# queso_dip_v4.net
KiCad netlist of a schematic drawn in EAGLE
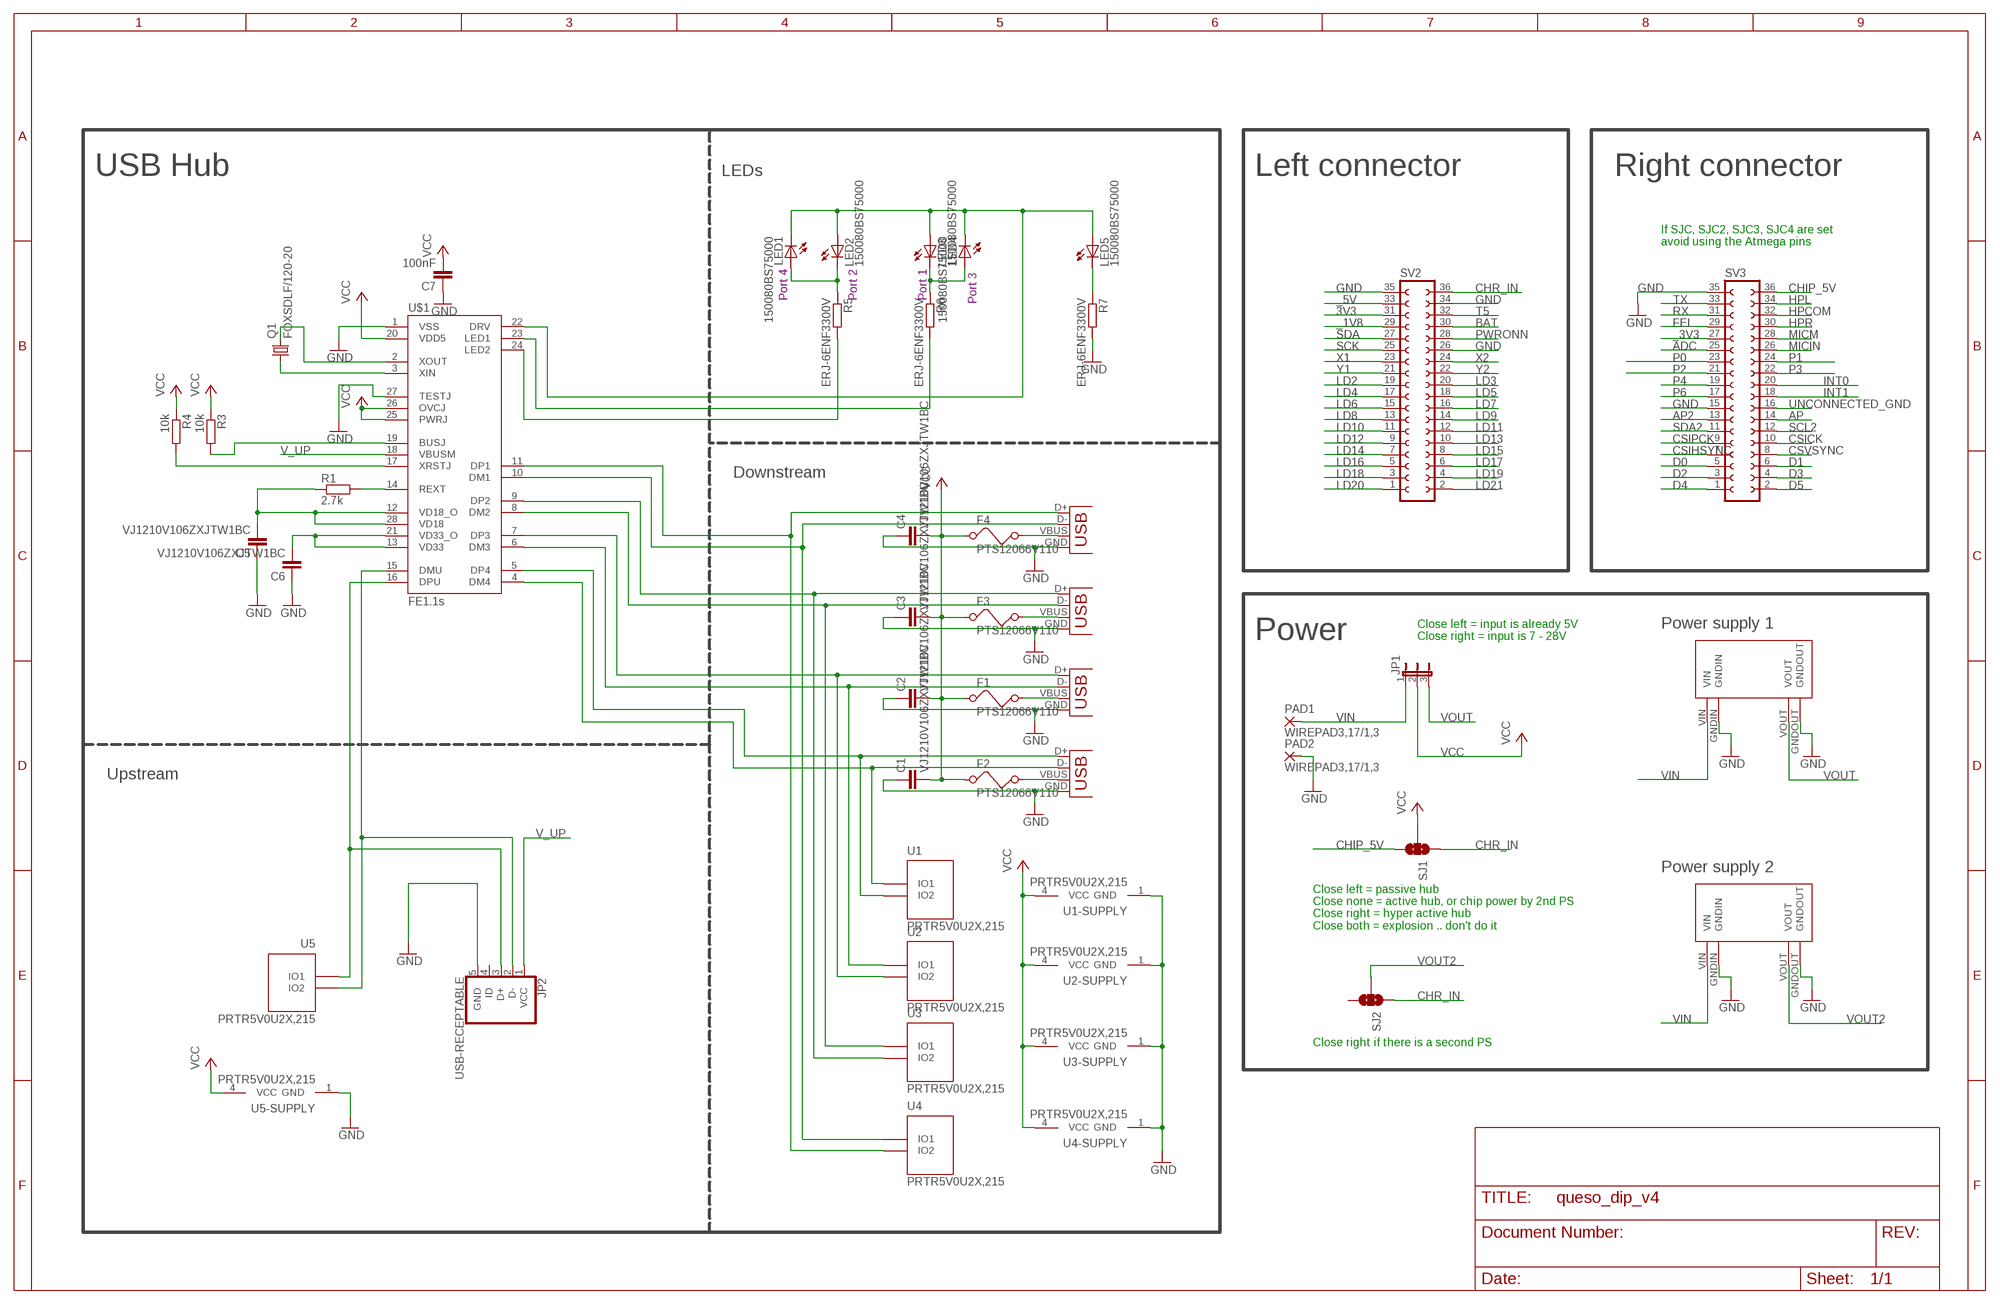
[diagram p0: schematic, sheet 1]

(export (version "E")
  (design (tool "Eeschema 10.0.6"))
  (components
    (comp (ref "C1")
      (value "VJ1210V106ZXJTW1BC")
      (footprint "eagle-import:C1210")
      (libsource (lib "eagle-import") (part "C-EUC1210"))
    )
    (comp (ref "C2")
      (value "VJ1210V106ZXJTW1BC")
      (footprint "eagle-import:C1210")
      (libsource (lib "eagle-import") (part "C-EUC1210"))
    )
    (comp (ref "C3")
      (value "VJ1210V106ZXJTW1BC")
      (footprint "eagle-import:C1210")
      (libsource (lib "eagle-import") (part "C-EUC1210"))
    )
    (comp (ref "C4")
      (value "VJ1210V106ZXJTW1BC")
      (footprint "eagle-import:C1210")
      (libsource (lib "eagle-import") (part "C-EUC1210"))
    )
    (comp (ref "C5")
      (value "VJ1210V106ZXJTW1BC")
      (footprint "eagle-import:C1210")
      (libsource (lib "eagle-import") (part "C-EUC1210"))
    )
    (comp (ref "C6")
      (value "VJ1210V106ZXJTW1BC")
      (footprint "eagle-import:C1210")
      (libsource (lib "eagle-import") (part "C-EUC1210"))
    )
    (comp (ref "C7")
      (value "100nF")
      (footprint "eagle-import:C0805")
      (libsource (lib "eagle-import") (part "C-EUC0805"))
    )
    (comp (ref "F1")
      (value "PTS12066V110")
      (footprint "eagle-import:1210")
      (libsource (lib "eagle-import") (part "FUSED"))
    )
    (comp (ref "F2")
      (value "PTS12066V110")
      (footprint "eagle-import:1210")
      (libsource (lib "eagle-import") (part "FUSED"))
    )
    (comp (ref "F3")
      (value "PTS12066V110")
      (footprint "eagle-import:1210")
      (libsource (lib "eagle-import") (part "FUSED"))
    )
    (comp (ref "F4")
      (value "PTS12066V110")
      (footprint "eagle-import:1210")
      (libsource (lib "eagle-import") (part "FUSED"))
    )
    (comp (ref "JP1")
      (value "JP2E")
      (footprint "eagle-import:JP2")
      (libsource (lib "eagle-import") (part "JP2E"))
    )
    (comp (ref "JP2")
      (value "USB-RECEPTABLE")
      (footprint "eagle-import:FCI-10103594-0001LF")
      (libsource (lib "eagle-import") (part "USB-RECEPTABLE"))
    )
    (comp (ref "LED1")
      (value "150080BS75000")
      (footprint "eagle-import:CHIP-LED0805")
      (libsource (lib "eagle-import") (part "LEDCHIP-LED0805"))
    )
    (comp (ref "LED2")
      (value "150080BS75000")
      (footprint "eagle-import:CHIP-LED0805")
      (libsource (lib "eagle-import") (part "LEDCHIP-LED0805"))
    )
    (comp (ref "LED3")
      (value "150080BS75000")
      (footprint "eagle-import:CHIP-LED0805")
      (libsource (lib "eagle-import") (part "LEDCHIP-LED0805"))
    )
    (comp (ref "LED4")
      (value "150080BS75000")
      (footprint "eagle-import:CHIP-LED0805")
      (libsource (lib "eagle-import") (part "LEDCHIP-LED0805"))
    )
    (comp (ref "LED5")
      (value "150080BS75000")
      (footprint "eagle-import:CHIP-LED0805")
      (libsource (lib "eagle-import") (part "LEDCHIP-LED0805"))
    )
    (comp (ref "PAD1")
      (value "WIREPAD3,17/1,3")
      (footprint "eagle-import:3,17_1,3")
      (libsource (lib "eagle-import") (part "WIREPAD3,17/1,3"))
    )
    (comp (ref "PAD2")
      (value "WIREPAD3,17/1,3")
      (footprint "eagle-import:3,17_1,3")
      (libsource (lib "eagle-import") (part "WIREPAD3,17/1,3"))
    )
    (comp (ref "Q1")
      (value "FOXSDLF/120-20")
      (footprint "eagle-import:SM49")
      (libsource (lib "eagle-import") (part "CRYSTALSM49"))
    )
    (comp (ref "R1")
      (value "2.7k")
      (footprint "eagle-import:R0805")
      (libsource (lib "eagle-import") (part "R-EU_R0805"))
    )
    (comp (ref "R3")
      (value "10k")
      (footprint "eagle-import:R0805")
      (libsource (lib "eagle-import") (part "R-EU_R0805"))
    )
    (comp (ref "R4")
      (value "10k")
      (footprint "eagle-import:R0805")
      (libsource (lib "eagle-import") (part "R-EU_R0805"))
    )
    (comp (ref "R5")
      (value "ERJ-6ENF3300V")
      (footprint "eagle-import:R0805")
      (libsource (lib "eagle-import") (part "R-EU_R0805"))
    )
    (comp (ref "R6")
      (value "ERJ-6ENF3300V")
      (footprint "eagle-import:R0805")
      (libsource (lib "eagle-import") (part "R-EU_R0805"))
    )
    (comp (ref "R7")
      (value "ERJ-6ENF3300V")
      (footprint "eagle-import:R0805")
      (libsource (lib "eagle-import") (part "R-EU_R0805"))
    )
    (comp (ref "SJ1")
      (value "SOLDERJUMPER_2WAYT")
      (footprint "eagle-import:SJ_2")
      (libsource (lib "eagle-import") (part "SOLDERJUMPER_2WAYT"))
    )
    (comp (ref "SJ2")
      (value "SOLDERJUMPER_2WAYT")
      (footprint "eagle-import:SJ_2")
      (libsource (lib "eagle-import") (part "SOLDERJUMPER_2WAYT"))
    )
    (comp (ref "SV2")
      (value "FE18-2")
      (footprint "eagle-import:FE18-2")
      (libsource (lib "eagle-import") (part "FE18-2"))
    )
    (comp (ref "SV3")
      (value "FE18-2")
      (footprint "eagle-import:FE18-2")
      (libsource (lib "eagle-import") (part "FE18-2"))
    )
    (comp (ref "U$1")
      (value "FE1.1S")
      (footprint "eagle-import:FE1.1S_SSOP-28")
      (libsource (lib "eagle-import") (part "FE1.1S"))
    )
    (comp (ref "U$3")
      (value "MP1584EN")
      (footprint "eagle-import:MP1584EN")
      (libsource (lib "eagle-import") (part "MP1584EN"))
    )
    (comp (ref "U$9")
      (value "MP1584EN")
      (footprint "eagle-import:MP1584EN")
      (libsource (lib "eagle-import") (part "MP1584EN"))
    )
    (comp (ref "U1")
      (value "PRTR5V0U2X,215")
      (footprint "eagle-import:SOT-143B")
      (fields (field (name "MANUFACTURER") "NXP Semiconductors"))
      (libsource (lib "eagle-import") (part "PRTR5V0U2X?"))
    )
    (comp (ref "U2")
      (value "PRTR5V0U2X,215")
      (footprint "eagle-import:SOT-143B")
      (fields (field (name "MANUFACTURER") "NXP Semiconductors"))
      (libsource (lib "eagle-import") (part "PRTR5V0U2X?"))
    )
    (comp (ref "U3")
      (value "PRTR5V0U2X,215")
      (footprint "eagle-import:SOT-143B")
      (fields (field (name "MANUFACTURER") "NXP Semiconductors"))
      (libsource (lib "eagle-import") (part "PRTR5V0U2X?"))
    )
    (comp (ref "U4")
      (value "PRTR5V0U2X,215")
      (footprint "eagle-import:SOT-143B")
      (fields (field (name "MANUFACTURER") "NXP Semiconductors"))
      (libsource (lib "eagle-import") (part "PRTR5V0U2X?"))
    )
    (comp (ref "U5")
      (value "PRTR5V0U2X,215")
      (footprint "eagle-import:SOT-143B")
      (fields (field (name "MANUFACTURER") "NXP Semiconductors"))
      (libsource (lib "eagle-import") (part "PRTR5V0U2X?"))
    )
    (comp (ref "X1")
      (value "USB-A-HU")
      (footprint "eagle-import:USB-A-HU")
      (libsource (lib "eagle-import") (part "USB-A-HU"))
    )
    (comp (ref "X2")
      (value "USB-A-HU")
      (footprint "eagle-import:USB-A-HU")
      (libsource (lib "eagle-import") (part "USB-A-HU"))
    )
    (comp (ref "X3")
      (value "USB-A-HU")
      (footprint "eagle-import:USB-A-HU")
      (libsource (lib "eagle-import") (part "USB-A-HU"))
    )
    (comp (ref "X4")
      (value "USB-A-HU")
      (footprint "eagle-import:USB-A-HU")
      (libsource (lib "eagle-import") (part "USB-A-HU"))
    )
  )
  (nets
    (net (code "1") (name "/3V3") (class "Default")
      (node (ref "SV2") (pin "31") (pinfunction "31_31") (pintype "passive"))
    )
    (net (code "2") (name "/ADC") (class "Default")
      (node (ref "SV3") (pin "25") (pinfunction "25_25") (pintype "passive"))
    )
    (net (code "3") (name "/AP") (class "Default")
      (node (ref "SV3") (pin "14") (pinfunction "14_14") (pintype "passive"))
    )
    (net (code "4") (name "/AP2") (class "Default")
      (node (ref "SV3") (pin "13") (pinfunction "13_13") (pintype "passive"))
    )
    (net (code "5") (name "/BAT") (class "Default")
      (node (ref "SV2") (pin "30") (pinfunction "30_30") (pintype "passive"))
    )
    (net (code "6") (name "/CHIP_5V") (class "Default")
      (node (ref "SJ1") (pin "3") (pinfunction "3_3") (pintype "passive"))
      (node (ref "SV3") (pin "36") (pinfunction "36_36") (pintype "passive"))
    )
    (net (code "7") (name "/CHR_IN") (class "Default")
      (node (ref "SJ1") (pin "1") (pinfunction "1_1") (pintype "passive"))
      (node (ref "SJ2") (pin "1") (pinfunction "1_1") (pintype "passive"))
      (node (ref "SV2") (pin "36") (pinfunction "36_36") (pintype "passive"))
    )
    (net (code "8") (name "/CSICK") (class "Default")
      (node (ref "SV3") (pin "10") (pinfunction "10_10") (pintype "passive"))
    )
    (net (code "9") (name "/CSIHSYNC") (class "Default")
      (node (ref "SV3") (pin "7") (pinfunction "7_7") (pintype "passive"))
    )
    (net (code "10") (name "/CSIPCK") (class "Default")
      (node (ref "SV3") (pin "9") (pinfunction "9_9") (pintype "passive"))
    )
    (net (code "11") (name "/CSVSYNC") (class "Default")
      (node (ref "SV3") (pin "8") (pinfunction "8_8") (pintype "passive"))
    )
    (net (code "12") (name "/D0") (class "Default")
      (node (ref "SV3") (pin "5") (pinfunction "5_5") (pintype "passive"))
    )
    (net (code "13") (name "/D1") (class "Default")
      (node (ref "SV3") (pin "6") (pinfunction "6_6") (pintype "passive"))
    )
    (net (code "14") (name "/D2") (class "Default")
      (node (ref "SV3") (pin "3") (pinfunction "3_3") (pintype "passive"))
    )
    (net (code "15") (name "/D3") (class "Default")
      (node (ref "SV3") (pin "4") (pinfunction "4_4") (pintype "passive"))
    )
    (net (code "16") (name "/D4") (class "Default")
      (node (ref "SV3") (pin "1") (pinfunction "1_1") (pintype "passive"))
    )
    (net (code "17") (name "/D5") (class "Default")
      (node (ref "SV3") (pin "2") (pinfunction "2_2") (pintype "passive"))
    )
    (net (code "18") (name "/FEL") (class "Default")
      (node (ref "SV3") (pin "29") (pinfunction "29_29") (pintype "passive"))
    )
    (net (code "19") (name "/HPCOM") (class "Default")
      (node (ref "SV3") (pin "32") (pinfunction "32_32") (pintype "passive"))
    )
    (net (code "20") (name "/HPL") (class "Default")
      (node (ref "SV3") (pin "34") (pinfunction "34_34") (pintype "passive"))
    )
    (net (code "21") (name "/HPR") (class "Default")
      (node (ref "SV3") (pin "30") (pinfunction "30_30") (pintype "passive"))
    )
    (net (code "22") (name "/INT0") (class "Default")
      (node (ref "SV3") (pin "20") (pinfunction "20_20") (pintype "passive"))
    )
    (net (code "23") (name "/INT1") (class "Default")
      (node (ref "SV3") (pin "18") (pinfunction "18_18") (pintype "passive"))
    )
    (net (code "24") (name "/LD2") (class "Default")
      (node (ref "SV2") (pin "19") (pinfunction "19_19") (pintype "passive"))
    )
    (net (code "25") (name "/LD3") (class "Default")
      (node (ref "SV2") (pin "20") (pinfunction "20_20") (pintype "passive"))
    )
    (net (code "26") (name "/LD4") (class "Default")
      (node (ref "SV2") (pin "17") (pinfunction "17_17") (pintype "passive"))
    )
    (net (code "27") (name "/LD5") (class "Default")
      (node (ref "SV2") (pin "18") (pinfunction "18_18") (pintype "passive"))
    )
    (net (code "28") (name "/LD6") (class "Default")
      (node (ref "SV2") (pin "15") (pinfunction "15_15") (pintype "passive"))
    )
    (net (code "29") (name "/LD7") (class "Default")
      (node (ref "SV2") (pin "16") (pinfunction "16_16") (pintype "passive"))
    )
    (net (code "30") (name "/LD8") (class "Default")
      (node (ref "SV2") (pin "13") (pinfunction "13_13") (pintype "passive"))
    )
    (net (code "31") (name "/LD9") (class "Default")
      (node (ref "SV2") (pin "14") (pinfunction "14_14") (pintype "passive"))
    )
    (net (code "32") (name "/LD10") (class "Default")
      (node (ref "SV2") (pin "11") (pinfunction "11_11") (pintype "passive"))
    )
    (net (code "33") (name "/LD11") (class "Default")
      (node (ref "SV2") (pin "12") (pinfunction "12_12") (pintype "passive"))
    )
    (net (code "34") (name "/LD12") (class "Default")
      (node (ref "SV2") (pin "9") (pinfunction "9_9") (pintype "passive"))
    )
    (net (code "35") (name "/LD13") (class "Default")
      (node (ref "SV2") (pin "10") (pinfunction "10_10") (pintype "passive"))
    )
    (net (code "36") (name "/LD14") (class "Default")
      (node (ref "SV2") (pin "7") (pinfunction "7_7") (pintype "passive"))
    )
    (net (code "37") (name "/LD15") (class "Default")
      (node (ref "SV2") (pin "8") (pinfunction "8_8") (pintype "passive"))
    )
    (net (code "38") (name "/LD16") (class "Default")
      (node (ref "SV2") (pin "5") (pinfunction "5_5") (pintype "passive"))
    )
    (net (code "39") (name "/LD17") (class "Default")
      (node (ref "SV2") (pin "6") (pinfunction "6_6") (pintype "passive"))
    )
    (net (code "40") (name "/LD18") (class "Default")
      (node (ref "SV2") (pin "3") (pinfunction "3_3") (pintype "passive"))
    )
    (net (code "41") (name "/LD19") (class "Default")
      (node (ref "SV2") (pin "4") (pinfunction "4_4") (pintype "passive"))
    )
    (net (code "42") (name "/LD20") (class "Default")
      (node (ref "SV2") (pin "1") (pinfunction "1_1") (pintype "passive"))
    )
    (net (code "43") (name "/LD21") (class "Default")
      (node (ref "SV2") (pin "2") (pinfunction "2_2") (pintype "passive"))
    )
    (net (code "44") (name "/MICIN") (class "Default")
      (node (ref "SV3") (pin "26") (pinfunction "26_26") (pintype "passive"))
    )
    (net (code "45") (name "/MICM") (class "Default")
      (node (ref "SV3") (pin "28") (pinfunction "28_28") (pintype "passive"))
    )
    (net (code "46") (name "/P0") (class "Default")
      (node (ref "SV3") (pin "23") (pinfunction "23_23") (pintype "passive"))
    )
    (net (code "47") (name "/P1") (class "Default")
      (node (ref "SV3") (pin "24") (pinfunction "24_24") (pintype "passive"))
    )
    (net (code "48") (name "/P2") (class "Default")
      (node (ref "SV3") (pin "21") (pinfunction "21_21") (pintype "passive"))
    )
    (net (code "49") (name "/P3") (class "Default")
      (node (ref "SV3") (pin "22") (pinfunction "22_22") (pintype "passive"))
    )
    (net (code "50") (name "/P4") (class "Default")
      (node (ref "SV3") (pin "19") (pinfunction "19_19") (pintype "passive"))
    )
    (net (code "51") (name "/P6") (class "Default")
      (node (ref "SV3") (pin "17") (pinfunction "17_17") (pintype "passive"))
    )
    (net (code "52") (name "/PWRONN") (class "Default")
      (node (ref "SV2") (pin "28") (pinfunction "28_28") (pintype "passive"))
    )
    (net (code "53") (name "/RX") (class "Default")
      (node (ref "SV3") (pin "31") (pinfunction "31_31") (pintype "passive"))
    )
    (net (code "54") (name "/SCK") (class "Default")
      (node (ref "SV2") (pin "25") (pinfunction "25_25") (pintype "passive"))
    )
    (net (code "55") (name "/SCL2") (class "Default")
      (node (ref "SV3") (pin "12") (pinfunction "12_12") (pintype "passive"))
    )
    (net (code "56") (name "/SDA") (class "Default")
      (node (ref "SV2") (pin "27") (pinfunction "27_27") (pintype "passive"))
    )
    (net (code "57") (name "/SDA2") (class "Default")
      (node (ref "SV3") (pin "11") (pinfunction "11_11") (pintype "passive"))
    )
    (net (code "58") (name "/T5") (class "Default")
      (node (ref "SV2") (pin "32") (pinfunction "32_32") (pintype "passive"))
    )
    (net (code "59") (name "/TX") (class "Default")
      (node (ref "SV3") (pin "33") (pinfunction "33_33") (pintype "passive"))
    )
    (net (code "60") (name "/UNCONNECTED_GND") (class "Default")
      (node (ref "SV3") (pin "16") (pinfunction "16_16") (pintype "passive"))
    )
    (net (code "61") (name "/VIN") (class "Default")
      (node (ref "JP1") (pin "1") (pinfunction "1_1") (pintype "passive"))
      (node (ref "PAD1") (pin "1") (pinfunction "P_1") (pintype "passive"))
      (node (ref "U$3") (pin "VIN") (pinfunction "VIN_VIN") (pintype "power_in"))
      (node (ref "U$9") (pin "VIN") (pinfunction "VIN_VIN") (pintype "power_in"))
    )
    (net (code "62") (name "/VOUT") (class "Default")
      (node (ref "JP1") (pin "3") (pinfunction "3_3") (pintype "passive"))
      (node (ref "U$9") (pin "VOUT") (pinfunction "VOUT_VOUT") (pintype "power_in"))
    )
    (net (code "63") (name "/VOUT2") (class "Default")
      (node (ref "SJ2") (pin "2") (pinfunction "2_2") (pintype "passive"))
      (node (ref "U$3") (pin "VOUT") (pinfunction "VOUT_VOUT") (pintype "power_in"))
    )
    (net (code "64") (name "/V_UP") (class "Default")
      (node (ref "JP2") (pin "1") (pinfunction "VCC_1") (pintype "bidirectional"))
      (node (ref "U$1") (pin "18") (pinfunction "VBUSM_18") (pintype "bidirectional"))
    )
    (net (code "65") (name "/X1") (class "Default")
      (node (ref "SV2") (pin "23") (pinfunction "23_23") (pintype "passive"))
    )
    (net (code "66") (name "/X2") (class "Default")
      (node (ref "SV2") (pin "24") (pinfunction "24_24") (pintype "passive"))
    )
    (net (code "67") (name "/Y1") (class "Default")
      (node (ref "SV2") (pin "21") (pinfunction "21_21") (pintype "passive"))
    )
    (net (code "68") (name "/Y2") (class "Default")
      (node (ref "SV2") (pin "22") (pinfunction "22_22") (pintype "passive"))
    )
    (net (code "69") (name "/_1V8") (class "Default")
      (node (ref "SV2") (pin "29") (pinfunction "29_29") (pintype "passive"))
    )
    (net (code "70") (name "/_3V3") (class "Default")
      (node (ref "SV3") (pin "27") (pinfunction "27_27") (pintype "passive"))
    )
    (net (code "71") (name "/_5V") (class "Default")
      (node (ref "SV2") (pin "33") (pinfunction "33_33") (pintype "passive"))
    )
    (net (code "72") (name "GND") (class "Default")
      (node (ref "C1") (pin "1") (pinfunction "1_1") (pintype "passive"))
      (node (ref "C2") (pin "1") (pinfunction "1_1") (pintype "passive"))
      (node (ref "C3") (pin "1") (pinfunction "1_1") (pintype "passive"))
      (node (ref "C4") (pin "1") (pinfunction "1_1") (pintype "passive"))
      (node (ref "C5") (pin "1") (pinfunction "1_1") (pintype "passive"))
      (node (ref "C6") (pin "1") (pinfunction "1_1") (pintype "passive"))
      (node (ref "C7") (pin "1") (pinfunction "1_1") (pintype "passive"))
      (node (ref "JP2") (pin "5") (pinfunction "GND_5") (pintype "bidirectional"))
      (node (ref "PAD2") (pin "1") (pinfunction "P_1") (pintype "passive"))
      (node (ref "R7") (pin "2") (pinfunction "2_2") (pintype "passive"))
      (node (ref "SV2") (pin "26") (pinfunction "26_26") (pintype "passive"))
      (node (ref "SV2") (pin "34") (pinfunction "34_34") (pintype "passive"))
      (node (ref "SV2") (pin "35") (pinfunction "35_35") (pintype "passive"))
      (node (ref "SV3") (pin "15") (pinfunction "15_15") (pintype "passive"))
      (node (ref "SV3") (pin "35") (pinfunction "35_35") (pintype "passive"))
      (node (ref "U$1") (pin "1") (pinfunction "VSS_1") (pintype "bidirectional"))
      (node (ref "U$1") (pin "27") (pinfunction "TESTJ_27") (pintype "bidirectional"))
      (node (ref "U$3") (pin "GNDIN") (pinfunction "GNDIN_GNDIN") (pintype "power_in"))
      (node (ref "U$3") (pin "GNDOUT") (pinfunction "GNDOUT_GNDOUT") (pintype "power_in"))
      (node (ref "U$9") (pin "GNDIN") (pinfunction "GNDIN_GNDIN") (pintype "power_in"))
      (node (ref "U$9") (pin "GNDOUT") (pinfunction "GNDOUT_GNDOUT") (pintype "power_in"))
      (node (ref "U1") (pin "1") (pinfunction "GND_1") (pintype "bidirectional"))
      (node (ref "U2") (pin "1") (pinfunction "GND_1") (pintype "bidirectional"))
      (node (ref "U3") (pin "1") (pinfunction "GND_1") (pintype "bidirectional"))
      (node (ref "U4") (pin "1") (pinfunction "GND_1") (pintype "bidirectional"))
      (node (ref "U5") (pin "1") (pinfunction "GND_1") (pintype "bidirectional"))
      (node (ref "X1") (pin "GND") (pinfunction "GND_GND") (pintype "bidirectional"))
      (node (ref "X2") (pin "GND") (pinfunction "GND_GND") (pintype "bidirectional"))
      (node (ref "X3") (pin "GND") (pinfunction "GND_GND") (pintype "bidirectional"))
      (node (ref "X4") (pin "GND") (pinfunction "GND_GND") (pintype "bidirectional"))
    )
    (net (code "73") (name "Net-(F1-Pad2)") (class "Default")
      (node (ref "F1") (pin "2") (pinfunction "2_2") (pintype "passive"))
      (node (ref "X2") (pin "VBUS") (pinfunction "VBUS_VBUS") (pintype "bidirectional"))
    )
    (net (code "74") (name "Net-(F2-Pad2)") (class "Default")
      (node (ref "F2") (pin "2") (pinfunction "2_2") (pintype "passive"))
      (node (ref "X1") (pin "VBUS") (pinfunction "VBUS_VBUS") (pintype "bidirectional"))
    )
    (net (code "75") (name "Net-(F3-Pad2)") (class "Default")
      (node (ref "F3") (pin "2") (pinfunction "2_2") (pintype "passive"))
      (node (ref "X3") (pin "VBUS") (pinfunction "VBUS_VBUS") (pintype "bidirectional"))
    )
    (net (code "76") (name "Net-(F4-Pad2)") (class "Default")
      (node (ref "F4") (pin "2") (pinfunction "2_2") (pintype "passive"))
      (node (ref "X4") (pin "VBUS") (pinfunction "VBUS_VBUS") (pintype "bidirectional"))
    )
    (net (code "77") (name "Net-(JP2-D+)") (class "Default")
      (node (ref "JP2") (pin "3") (pinfunction "D+_3") (pintype "bidirectional"))
      (node (ref "U$1") (pin "16") (pinfunction "DPU_16") (pintype "bidirectional"))
      (node (ref "U5") (pin "2") (pinfunction "IO1_2") (pintype "bidirectional"))
    )
    (net (code "78") (name "Net-(JP2-D-)") (class "Default")
      (node (ref "JP2") (pin "2") (pinfunction "D-_2") (pintype "bidirectional"))
      (node (ref "U$1") (pin "15") (pinfunction "DMU_15") (pintype "bidirectional"))
      (node (ref "U5") (pin "3") (pinfunction "IO2_3") (pintype "bidirectional"))
    )
    (net (code "79") (name "Net-(LED1-PadA)") (class "Default")
      (node (ref "LED1") (pin "A") (pinfunction "A_A") (pintype "passive"))
      (node (ref "LED2") (pin "C") (pinfunction "C_C") (pintype "passive"))
      (node (ref "R5") (pin "1") (pinfunction "1_1") (pintype "passive"))
    )
    (net (code "80") (name "Net-(LED3-PadC)") (class "Default")
      (node (ref "LED3") (pin "C") (pinfunction "C_C") (pintype "passive"))
      (node (ref "LED4") (pin "A") (pinfunction "A_A") (pintype "passive"))
      (node (ref "R6") (pin "1") (pinfunction "1_1") (pintype "passive"))
    )
    (net (code "81") (name "Net-(LED5-PadC)") (class "Default")
      (node (ref "LED5") (pin "C") (pinfunction "C_C") (pintype "passive"))
      (node (ref "R7") (pin "1") (pinfunction "1_1") (pintype "passive"))
    )
    (net (code "82") (name "Net-(U$1-BUSJ)") (class "Default")
      (node (ref "R3") (pin "2") (pinfunction "2_2") (pintype "passive"))
      (node (ref "U$1") (pin "19") (pinfunction "BUSJ_19") (pintype "bidirectional"))
    )
    (net (code "83") (name "Net-(U$1-DM1)") (class "Default")
      (node (ref "U$1") (pin "10") (pinfunction "DM1_10") (pintype "bidirectional"))
      (node (ref "U4") (pin "2") (pinfunction "IO1_2") (pintype "bidirectional"))
      (node (ref "X4") (pin "D-") (pinfunction "D-_D-") (pintype "bidirectional"))
    )
    (net (code "84") (name "Net-(U$1-DM2)") (class "Default")
      (node (ref "U$1") (pin "8") (pinfunction "DM2_8") (pintype "bidirectional"))
      (node (ref "U3") (pin "2") (pinfunction "IO1_2") (pintype "bidirectional"))
      (node (ref "X3") (pin "D-") (pinfunction "D-_D-") (pintype "bidirectional"))
    )
    (net (code "85") (name "Net-(U$1-DM3)") (class "Default")
      (node (ref "U$1") (pin "6") (pinfunction "DM3_6") (pintype "bidirectional"))
      (node (ref "U2") (pin "2") (pinfunction "IO1_2") (pintype "bidirectional"))
      (node (ref "X2") (pin "D-") (pinfunction "D-_D-") (pintype "bidirectional"))
    )
    (net (code "86") (name "Net-(U$1-DM4)") (class "Default")
      (node (ref "U$1") (pin "4") (pinfunction "DM4_4") (pintype "bidirectional"))
      (node (ref "U1") (pin "2") (pinfunction "IO1_2") (pintype "bidirectional"))
      (node (ref "X1") (pin "D-") (pinfunction "D-_D-") (pintype "bidirectional"))
    )
    (net (code "87") (name "Net-(U$1-DP1)") (class "Default")
      (node (ref "U$1") (pin "11") (pinfunction "DP1_11") (pintype "bidirectional"))
      (node (ref "U4") (pin "3") (pinfunction "IO2_3") (pintype "bidirectional"))
      (node (ref "X4") (pin "D+") (pinfunction "D+_D+") (pintype "bidirectional"))
    )
    (net (code "88") (name "Net-(U$1-DP2)") (class "Default")
      (node (ref "U$1") (pin "9") (pinfunction "DP2_9") (pintype "bidirectional"))
      (node (ref "U3") (pin "3") (pinfunction "IO2_3") (pintype "bidirectional"))
      (node (ref "X3") (pin "D+") (pinfunction "D+_D+") (pintype "bidirectional"))
    )
    (net (code "89") (name "Net-(U$1-DP3)") (class "Default")
      (node (ref "U$1") (pin "7") (pinfunction "DP3_7") (pintype "bidirectional"))
      (node (ref "U2") (pin "3") (pinfunction "IO2_3") (pintype "bidirectional"))
      (node (ref "X2") (pin "D+") (pinfunction "D+_D+") (pintype "bidirectional"))
    )
    (net (code "90") (name "Net-(U$1-DP4)") (class "Default")
      (node (ref "U$1") (pin "5") (pinfunction "DP4_5") (pintype "bidirectional"))
      (node (ref "U1") (pin "3") (pinfunction "IO2_3") (pintype "bidirectional"))
      (node (ref "X1") (pin "D+") (pinfunction "D+_D+") (pintype "bidirectional"))
    )
    (net (code "91") (name "Net-(U$1-DRV)") (class "Default")
      (node (ref "LED1") (pin "C") (pinfunction "C_C") (pintype "passive"))
      (node (ref "LED2") (pin "A") (pinfunction "A_A") (pintype "passive"))
      (node (ref "LED3") (pin "A") (pinfunction "A_A") (pintype "passive"))
      (node (ref "LED4") (pin "C") (pinfunction "C_C") (pintype "passive"))
      (node (ref "LED5") (pin "A") (pinfunction "A_A") (pintype "passive"))
      (node (ref "U$1") (pin "22") (pinfunction "DRV_22") (pintype "bidirectional"))
    )
    (net (code "92") (name "Net-(U$1-LED1)") (class "Default")
      (node (ref "R6") (pin "2") (pinfunction "2_2") (pintype "passive"))
      (node (ref "U$1") (pin "23") (pinfunction "LED1_23") (pintype "bidirectional"))
    )
    (net (code "93") (name "Net-(U$1-LED2)") (class "Default")
      (node (ref "R5") (pin "2") (pinfunction "2_2") (pintype "passive"))
      (node (ref "U$1") (pin "24") (pinfunction "LED2_24") (pintype "bidirectional"))
    )
    (net (code "94") (name "Net-(U$1-REXT)") (class "Default")
      (node (ref "R1") (pin "2") (pinfunction "2_2") (pintype "passive"))
      (node (ref "U$1") (pin "14") (pinfunction "REXT_14") (pintype "bidirectional"))
    )
    (net (code "95") (name "Net-(U$1-VD18)") (class "Default")
      (node (ref "C5") (pin "2") (pinfunction "2_2") (pintype "passive"))
      (node (ref "R1") (pin "1") (pinfunction "1_1") (pintype "passive"))
      (node (ref "U$1") (pin "12") (pinfunction "VD18_O_12") (pintype "bidirectional"))
      (node (ref "U$1") (pin "28") (pinfunction "VD18_28") (pintype "bidirectional"))
    )
    (net (code "96") (name "Net-(U$1-VD33)") (class "Default")
      (node (ref "C6") (pin "2") (pinfunction "2_2") (pintype "passive"))
      (node (ref "U$1") (pin "13") (pinfunction "VD33_13") (pintype "bidirectional"))
      (node (ref "U$1") (pin "21") (pinfunction "VD33_O_21") (pintype "bidirectional"))
    )
    (net (code "97") (name "Net-(U$1-XIN)") (class "Default")
      (node (ref "Q1") (pin "1") (pinfunction "1_1") (pintype "passive"))
      (node (ref "U$1") (pin "3") (pinfunction "XIN_3") (pintype "bidirectional"))
    )
    (net (code "98") (name "Net-(U$1-XOUT)") (class "Default")
      (node (ref "Q1") (pin "2") (pinfunction "2_2") (pintype "passive"))
      (node (ref "U$1") (pin "2") (pinfunction "XOUT_2") (pintype "bidirectional"))
    )
    (net (code "99") (name "Net-(U$1-XRSTJ)") (class "Default")
      (node (ref "R4") (pin "2") (pinfunction "2_2") (pintype "passive"))
      (node (ref "U$1") (pin "17") (pinfunction "XRSTJ_17") (pintype "bidirectional"))
    )
    (net (code "100") (name "VCC") (class "Default")
      (node (ref "C1") (pin "2") (pinfunction "2_2") (pintype "passive"))
      (node (ref "C2") (pin "2") (pinfunction "2_2") (pintype "passive"))
      (node (ref "C3") (pin "2") (pinfunction "2_2") (pintype "passive"))
      (node (ref "C4") (pin "2") (pinfunction "2_2") (pintype "passive"))
      (node (ref "C7") (pin "2") (pinfunction "2_2") (pintype "passive"))
      (node (ref "F1") (pin "1") (pinfunction "1_1") (pintype "passive"))
      (node (ref "F2") (pin "1") (pinfunction "1_1") (pintype "passive"))
      (node (ref "F3") (pin "1") (pinfunction "1_1") (pintype "passive"))
      (node (ref "F4") (pin "1") (pinfunction "1_1") (pintype "passive"))
      (node (ref "JP1") (pin "2") (pinfunction "2_2") (pintype "passive"))
      (node (ref "R3") (pin "1") (pinfunction "1_1") (pintype "passive"))
      (node (ref "R4") (pin "1") (pinfunction "1_1") (pintype "passive"))
      (node (ref "SJ1") (pin "2") (pinfunction "2_2") (pintype "passive"))
      (node (ref "U$1") (pin "20") (pinfunction "VDD5_20") (pintype "bidirectional"))
      (node (ref "U$1") (pin "25") (pinfunction "PWRJ_25") (pintype "bidirectional"))
      (node (ref "U$1") (pin "26") (pinfunction "OVCJ_26") (pintype "bidirectional"))
      (node (ref "U1") (pin "4") (pinfunction "VCC_4") (pintype "bidirectional"))
      (node (ref "U2") (pin "4") (pinfunction "VCC_4") (pintype "bidirectional"))
      (node (ref "U3") (pin "4") (pinfunction "VCC_4") (pintype "bidirectional"))
      (node (ref "U4") (pin "4") (pinfunction "VCC_4") (pintype "bidirectional"))
      (node (ref "U5") (pin "4") (pinfunction "VCC_4") (pintype "bidirectional"))
    )
    (net (code "101") (name "unconnected-(JP2-ID-Pad4)") (class "Default")
      (node (ref "JP2") (pin "4") (pinfunction "ID_4") (pintype "bidirectional"))
    )
    (net (code "102") (name "unconnected-(SJ2-Pad3)") (class "Default")
      (node (ref "SJ2") (pin "3") (pinfunction "3_3") (pintype "passive"))
    )
  )
)
